# Power.net
KiCad netlist of a schematic drawn in Altium Designer
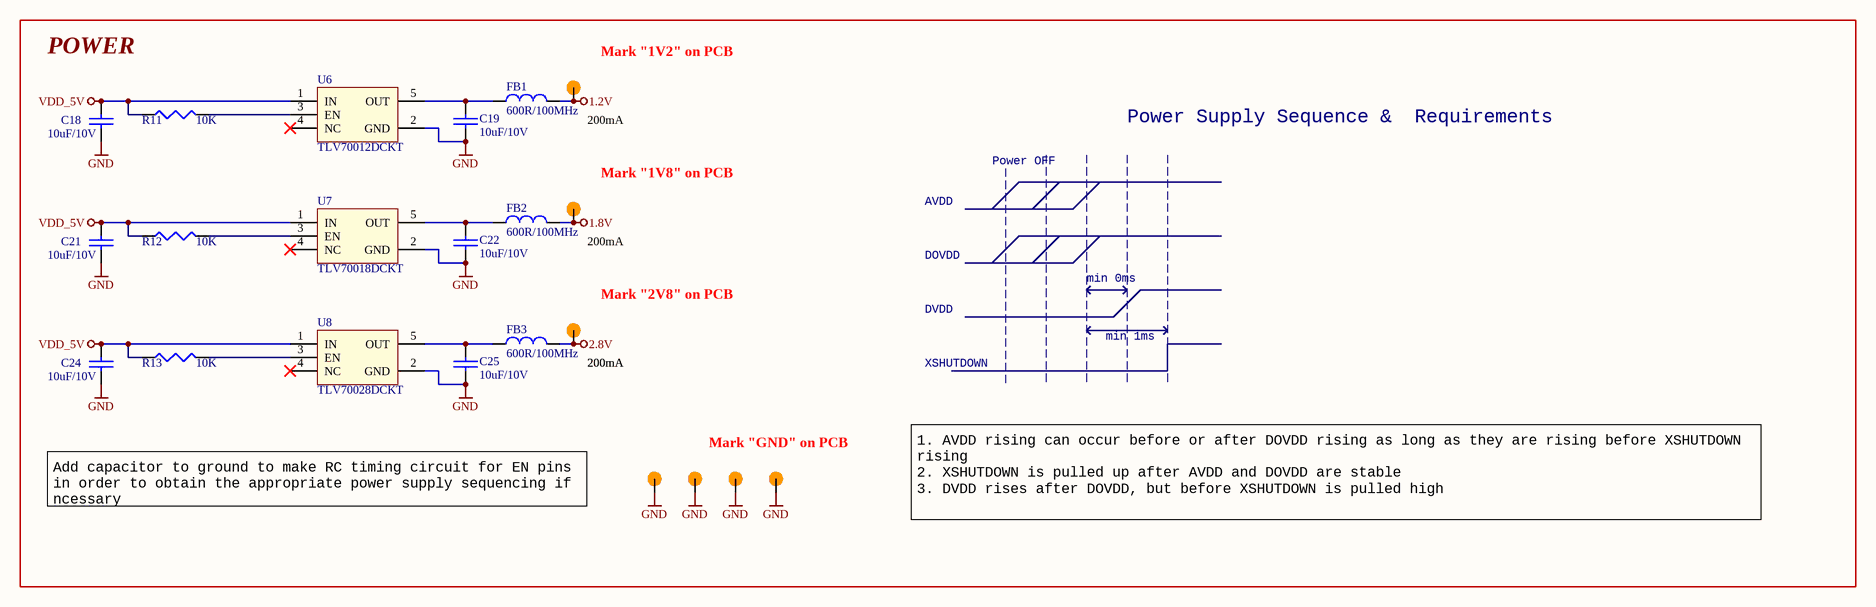
[diagram p0: Power.SchDoc]

(export (version "E")
  (design (tool "Eeschema 10.0.6"))
  (components
    (comp (ref "C18")
      (value "10uF/10V")
      (footprint "0603")
      (description "CC0603MRX5R5BB106  SMD Multilayer Ceramic Capacitor, 0603 [1608 Metric], 10 µF, 6.3 V, ± 20%, X5R")
      (libsource (lib "MV0250_R0M0E0") (part "CAP"))
    )
    (comp (ref "C19")
      (value "10uF/10V")
      (footprint "0603")
      (description "CC0603MRX5R5BB106  SMD Multilayer Ceramic Capacitor, 0603 [1608 Metric], 10 µF, 6.3 V, ± 20%, X5R")
      (libsource (lib "MV0250_R0M0E0") (part "CAP"))
    )
    (comp (ref "C21")
      (value "10uF/10V")
      (footprint "0603")
      (description "CC0603MRX5R5BB106  SMD Multilayer Ceramic Capacitor, 0603 [1608 Metric], 10 µF, 6.3 V, ± 20%, X5R")
      (libsource (lib "MV0250_R0M0E0") (part "CAP"))
    )
    (comp (ref "C22")
      (value "10uF/10V")
      (footprint "0603")
      (description "CC0603MRX5R5BB106  SMD Multilayer Ceramic Capacitor, 0603 [1608 Metric], 10 µF, 6.3 V, ± 20%, X5R")
      (libsource (lib "MV0250_R0M0E0") (part "CAP"))
    )
    (comp (ref "C24")
      (value "10uF/10V")
      (footprint "0603")
      (description "CC0603MRX5R5BB106  SMD Multilayer Ceramic Capacitor, 0603 [1608 Metric], 10 µF, 6.3 V, ± 20%, X5R")
      (libsource (lib "MV0250_R0M0E0") (part "CAP"))
    )
    (comp (ref "C25")
      (value "10uF/10V")
      (footprint "0603")
      (description "CC0603MRX5R5BB106  SMD Multilayer Ceramic Capacitor, 0603 [1608 Metric], 10 µF, 6.3 V, ± 20%, X5R")
      (libsource (lib "MV0250_R0M0E0") (part "CAP"))
    )
    (comp (ref "FB1")
      (value "600R/100MHz")
      (footprint "0805")
      (description "Ferrite Bead")
      (libsource (lib "MV0250_R0M0E0") (part "INDUCTANCE1"))
    )
    (comp (ref "FB2")
      (value "600R/100MHz")
      (footprint "0805")
      (description "Ferrite Bead")
      (libsource (lib "MV0250_R0M0E0") (part "INDUCTANCE1"))
    )
    (comp (ref "FB3")
      (value "600R/100MHz")
      (footprint "0805")
      (description "Ferrite Bead")
      (libsource (lib "MV0250_R0M0E0") (part "INDUCTANCE1"))
    )
    (comp (ref "R11")
      (value "10K")
      (footprint "0603")
      (description "SMD Chip Resistor, 10 kohm, 75 V, 0603 [1608 Metric], 100 mW, ± 1%")
      (libsource (lib "MV0250_R0M0E0") (part "RES1"))
    )
    (comp (ref "R12")
      (value "10K")
      (footprint "0603")
      (description "SMD Chip Resistor, 10 kohm, 75 V, 0603 [1608 Metric], 100 mW, ± 1%")
      (libsource (lib "MV0250_R0M0E0") (part "RES1"))
    )
    (comp (ref "R13")
      (value "10K")
      (footprint "0603")
      (description "SMD Chip Resistor, 10 kohm, 75 V, 0603 [1608 Metric], 100 mW, ± 1%")
      (libsource (lib "MV0250_R0M0E0") (part "RES1"))
    )
    (comp (ref "TP7")
      (value "TP_SMD")
      (footprint "TP_0.75MM_SMD_NO-SILK")
      (description "circular pad test point, SMD")
      (libsource (lib "Luxonis") (part "TP_SMD"))
    )
    (comp (ref "TP8")
      (value "TP_SMD")
      (footprint "TP_0.75MM_SMD_NO-SILK")
      (description "circular pad test point, SMD")
      (libsource (lib "Luxonis") (part "TP_SMD"))
    )
    (comp (ref "TP9")
      (value "TP_SMD")
      (footprint "TP_0.75MM_SMD_NO-SILK")
      (description "circular pad test point, SMD")
      (libsource (lib "Luxonis") (part "TP_SMD"))
    )
    (comp (ref "TP10")
      (value "TP_SMD")
      (footprint "TP_0.75MM_SMD_NO-SILK")
      (description "circular pad test point, SMD")
      (libsource (lib "Luxonis") (part "TP_SMD"))
    )
    (comp (ref "TP11")
      (value "TP_SMD")
      (footprint "TP_0.75MM_SMD_NO-SILK")
      (description "circular pad test point, SMD")
      (libsource (lib "Luxonis") (part "TP_SMD"))
    )
    (comp (ref "TP12")
      (value "TP_SMD")
      (footprint "TP_0.75MM_SMD_NO-SILK")
      (description "circular pad test point, SMD")
      (libsource (lib "Luxonis") (part "TP_SMD"))
    )
    (comp (ref "TP13")
      (value "TP_SMD")
      (footprint "TP_0.75MM_SMD_NO-SILK")
      (description "circular pad test point, SMD")
      (libsource (lib "Luxonis") (part "TP_SMD"))
    )
    (comp (ref "U6")
      (value "TLV70012DCKT")
      (footprint "SC70-5")
      (description "LDO, 200MA, 1.2V, 5SC70")
      (libsource (lib "MV0250_R0M0E0") (part "TLV70012DCKT"))
    )
    (comp (ref "U7")
      (value "TLV70018DCKT")
      (footprint "SC70-5")
      (description "LDO, 200MA, 1.8V, 5SC70")
      (libsource (lib "MV0250_R0M0E0") (part "TLV70018DCKT"))
    )
    (comp (ref "U8")
      (value "TLV70028DCKT")
      (footprint "SC70-5")
      (description "LDO, 200MA, 2.8V, 5SC70")
      (libsource (lib "MV0250_R0M0E0") (part "TLV70028DCKT"))
    )
  )
  (nets
    (net (code "1") (name "1.2V") (class "Default")
      (node (ref "FB1") (pin "2") (pinfunction "2_2") (pintype "passive"))
      (node (ref "TP7") (pin "1") (pintype "passive"))
    )
    (net (code "2") (name "1.8V") (class "Default")
      (node (ref "FB2") (pin "2") (pinfunction "2_2") (pintype "passive"))
      (node (ref "TP8") (pin "1") (pintype "passive"))
    )
    (net (code "3") (name "2.8V") (class "Default")
      (node (ref "FB3") (pin "2") (pinfunction "2_2") (pintype "passive"))
      (node (ref "TP9") (pin "1") (pintype "passive"))
    )
    (net (code "4") (name "GND") (class "Default")
      (node (ref "C18") (pin "2") (pinfunction "2_2") (pintype "passive"))
      (node (ref "C19") (pin "2") (pinfunction "2_2") (pintype "passive"))
      (node (ref "C21") (pin "2") (pinfunction "2_2") (pintype "passive"))
      (node (ref "C22") (pin "2") (pinfunction "2_2") (pintype "passive"))
      (node (ref "C24") (pin "2") (pinfunction "2_2") (pintype "passive"))
      (node (ref "C25") (pin "2") (pinfunction "2_2") (pintype "passive"))
      (node (ref "TP10") (pin "1") (pintype "passive"))
      (node (ref "TP11") (pin "1") (pintype "passive"))
      (node (ref "TP12") (pin "1") (pintype "passive"))
      (node (ref "TP13") (pin "1") (pintype "passive"))
      (node (ref "U6") (pin "2") (pinfunction "GND_2") (pintype "passive"))
      (node (ref "U7") (pin "2") (pinfunction "GND_2") (pintype "passive"))
      (node (ref "U8") (pin "2") (pinfunction "GND_2") (pintype "passive"))
    )
    (net (code "5") (name "Net-(U6-EN)") (class "Default")
      (node (ref "R11") (pin "2") (pintype "passive"))
      (node (ref "U6") (pin "3") (pinfunction "EN_3") (pintype "passive"))
    )
    (net (code "6") (name "Net-(U6-OUT)") (class "Default")
      (node (ref "C19") (pin "1") (pinfunction "1_1") (pintype "passive"))
      (node (ref "FB1") (pin "1") (pinfunction "1_1") (pintype "passive"))
      (node (ref "U6") (pin "5") (pinfunction "OUT_5") (pintype "passive"))
    )
    (net (code "7") (name "Net-(U7-EN)") (class "Default")
      (node (ref "R12") (pin "2") (pintype "passive"))
      (node (ref "U7") (pin "3") (pinfunction "EN_3") (pintype "passive"))
    )
    (net (code "8") (name "Net-(U7-OUT)") (class "Default")
      (node (ref "C22") (pin "1") (pinfunction "1_1") (pintype "passive"))
      (node (ref "FB2") (pin "1") (pinfunction "1_1") (pintype "passive"))
      (node (ref "U7") (pin "5") (pinfunction "OUT_5") (pintype "passive"))
    )
    (net (code "9") (name "Net-(U8-EN)") (class "Default")
      (node (ref "R13") (pin "2") (pintype "passive"))
      (node (ref "U8") (pin "3") (pinfunction "EN_3") (pintype "passive"))
    )
    (net (code "10") (name "Net-(U8-OUT)") (class "Default")
      (node (ref "C25") (pin "1") (pinfunction "1_1") (pintype "passive"))
      (node (ref "FB3") (pin "1") (pinfunction "1_1") (pintype "passive"))
      (node (ref "U8") (pin "5") (pinfunction "OUT_5") (pintype "passive"))
    )
    (net (code "11") (name "VDD_5V") (class "Default")
      (node (ref "C18") (pin "1") (pinfunction "1_1") (pintype "passive"))
      (node (ref "C21") (pin "1") (pinfunction "1_1") (pintype "passive"))
      (node (ref "C24") (pin "1") (pinfunction "1_1") (pintype "passive"))
      (node (ref "R11") (pin "1") (pintype "passive"))
      (node (ref "R12") (pin "1") (pintype "passive"))
      (node (ref "R13") (pin "1") (pintype "passive"))
      (node (ref "U6") (pin "1") (pinfunction "IN_1") (pintype "passive"))
      (node (ref "U7") (pin "1") (pinfunction "IN_1") (pintype "passive"))
      (node (ref "U8") (pin "1") (pinfunction "IN_1") (pintype "passive"))
    )
    (net (code "12") (name "unconnected-(U6-NC-Pad4)") (class "Default")
      (node (ref "U6") (pin "4") (pinfunction "NC_4") (pintype "passive+no_connect"))
    )
    (net (code "13") (name "unconnected-(U7-NC-Pad4)") (class "Default")
      (node (ref "U7") (pin "4") (pinfunction "NC_4") (pintype "passive+no_connect"))
    )
    (net (code "14") (name "unconnected-(U8-NC-Pad4)") (class "Default")
      (node (ref "U8") (pin "4") (pinfunction "NC_4") (pintype "passive+no_connect"))
    )
  )
)
